# SAE_Shifter_Schem_no_micro.net
KiCad netlist of a schematic drawn in EAGLE
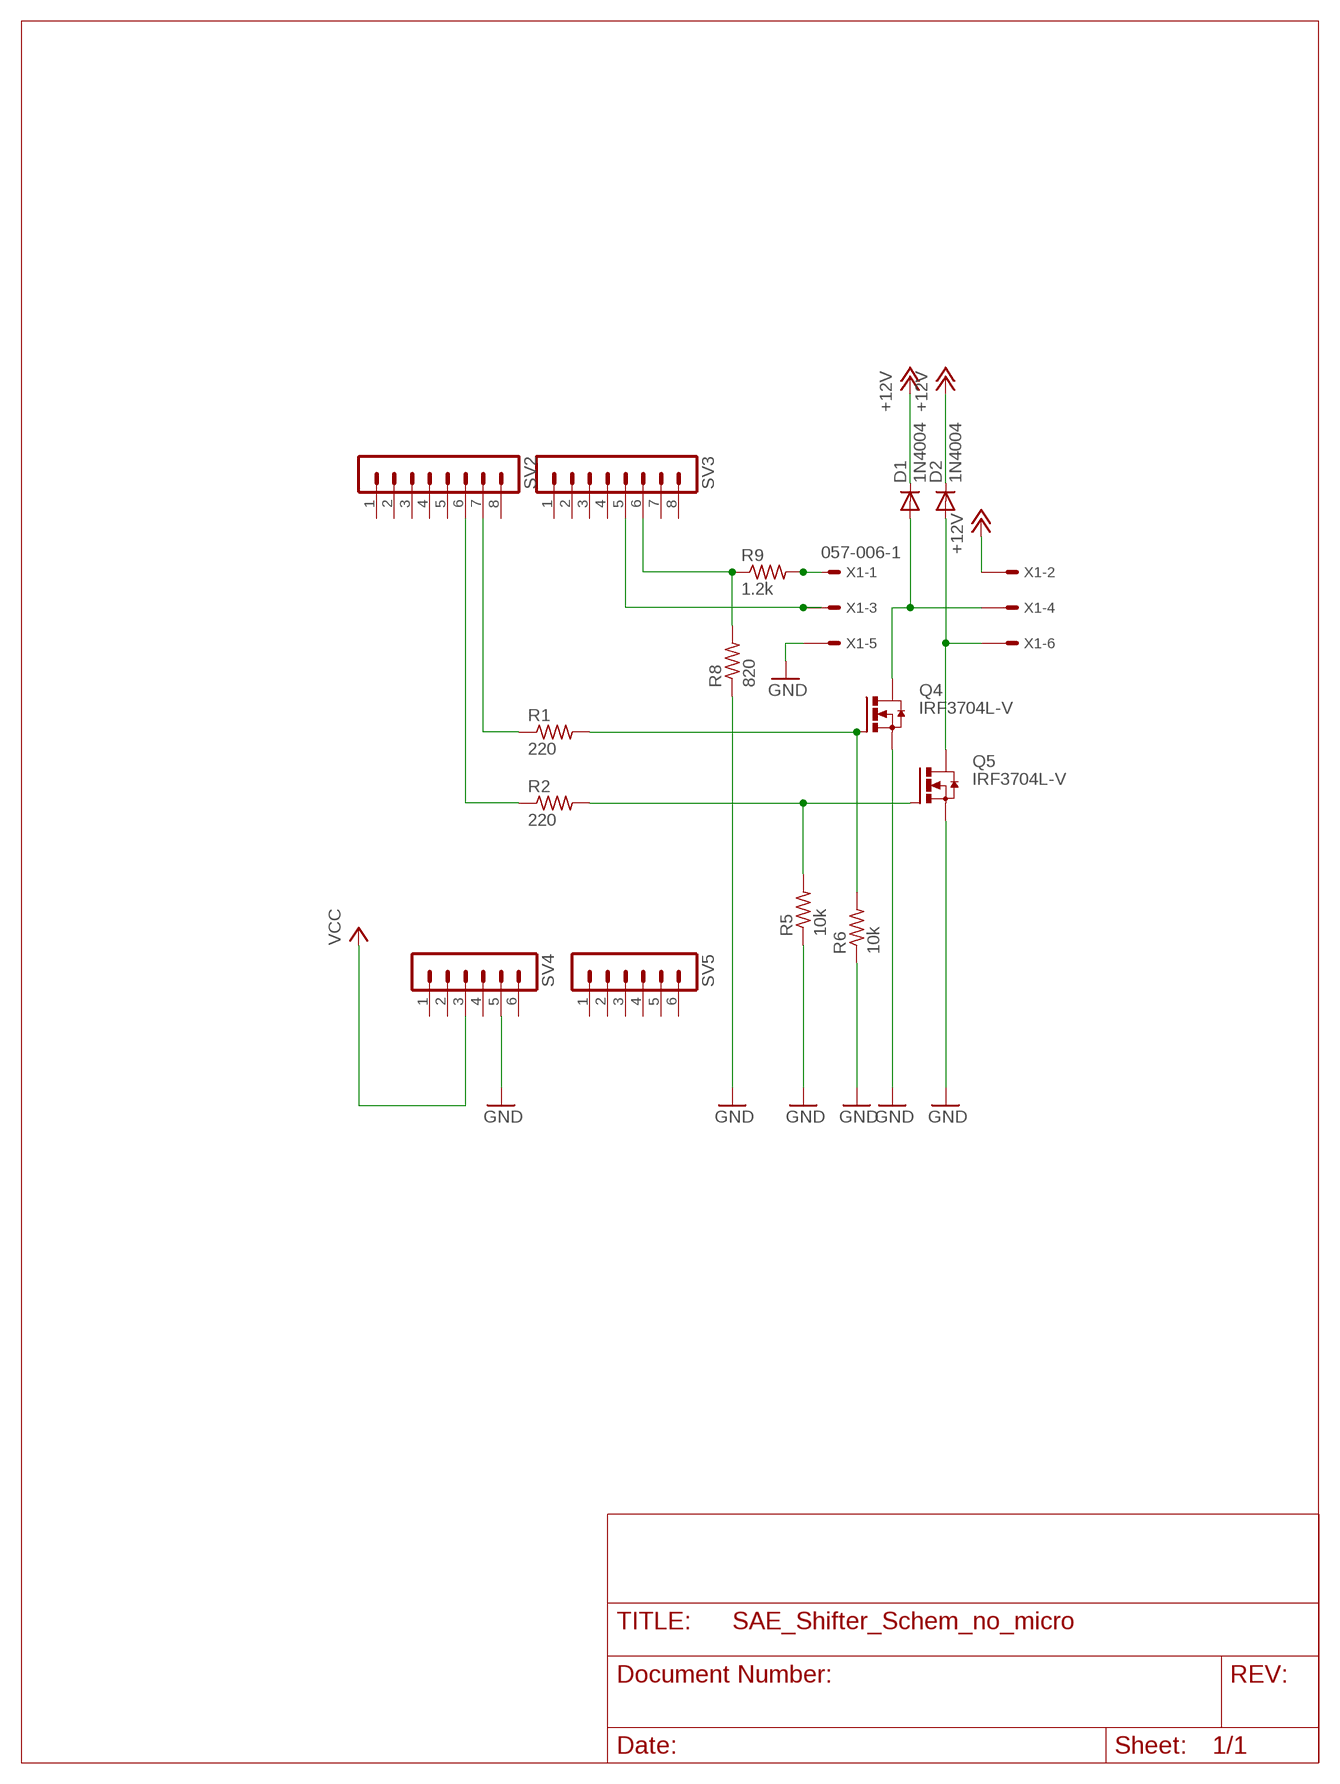
[diagram p0: schematic, sheet 1]

(export (version "E")
  (design (tool "Eeschema 10.0.6"))
  (components
    (comp (ref "D1")
      (value "1N4004")
      (footprint "eagle-import:DO41-10")
      (libsource (lib "eagle-import") (part "1N4004"))
    )
    (comp (ref "D2")
      (value "1N4004")
      (footprint "eagle-import:DO41-10")
      (libsource (lib "eagle-import") (part "1N4004"))
    )
    (comp (ref "Q4")
      (value "IRF3704L-V")
      (footprint "eagle-import:TO262-V")
      (libsource (lib "eagle-import") (part "IRF3704L-V"))
    )
    (comp (ref "Q5")
      (value "IRF3704L-V")
      (footprint "eagle-import:TO262-V")
      (libsource (lib "eagle-import") (part "IRF3704L-V"))
    )
    (comp (ref "R1")
      (value "220")
      (footprint "eagle-import:0207_10")
      (libsource (lib "eagle-import") (part "R-US_0207/10"))
    )
    (comp (ref "R2")
      (value "220")
      (footprint "eagle-import:0207_10")
      (libsource (lib "eagle-import") (part "R-US_0207/10"))
    )
    (comp (ref "R5")
      (value "10k")
      (footprint "eagle-import:0207_10")
      (libsource (lib "eagle-import") (part "R-US_0207/10"))
    )
    (comp (ref "R6")
      (value "10k")
      (footprint "eagle-import:0207_10")
      (libsource (lib "eagle-import") (part "R-US_0207/10"))
    )
    (comp (ref "R8")
      (value "820")
      (footprint "eagle-import:0207_10")
      (libsource (lib "eagle-import") (part "R-US_0207/10"))
    )
    (comp (ref "R9")
      (value "1.2k")
      (footprint "eagle-import:0207_10")
      (libsource (lib "eagle-import") (part "R-US_0207/10"))
    )
    (comp (ref "SV2")
      (value "MA08-1")
      (footprint "eagle-import:MA08-1")
      (libsource (lib "eagle-import") (part "MA08-1"))
    )
    (comp (ref "SV3")
      (value "MA08-1")
      (footprint "eagle-import:MA08-1")
      (libsource (lib "eagle-import") (part "MA08-1"))
    )
    (comp (ref "SV4")
      (value "MA06-1")
      (footprint "eagle-import:MA06-1")
      (libsource (lib "eagle-import") (part "MA06-1"))
    )
    (comp (ref "SV5")
      (value "MA06-1")
      (footprint "eagle-import:MA06-1")
      (libsource (lib "eagle-import") (part "MA06-1"))
    )
    (comp (ref "X1")
      (value "057-006-1")
      (footprint "eagle-import:057-006-1")
      (libsource (lib "eagle-import") (part "057-006-1"))
    )
  )
  (nets
    (net (code "1") (name "+12V") (class "Default")
      (node (ref "D1") (pin "C") (pinfunction "C_C") (pintype "passive"))
      (node (ref "D2") (pin "C") (pinfunction "C_C") (pintype "passive"))
      (node (ref "X1") (pin "2") (pinfunction "S_2") (pintype "passive"))
    )
    (net (code "2") (name "GND") (class "Default")
      (node (ref "Q4") (pin "3") (pinfunction "S_3") (pintype "passive"))
      (node (ref "Q5") (pin "3") (pinfunction "S_3") (pintype "passive"))
      (node (ref "R5") (pin "1") (pinfunction "1_1") (pintype "passive"))
      (node (ref "R6") (pin "1") (pinfunction "1_1") (pintype "passive"))
      (node (ref "R8") (pin "1") (pinfunction "1_1") (pintype "passive"))
      (node (ref "SV4") (pin "5") (pinfunction "5_5") (pintype "passive"))
      (node (ref "X1") (pin "5") (pinfunction "S_5") (pintype "passive"))
    )
    (net (code "3") (name "Net-(Q4-D)") (class "Default")
      (node (ref "D1") (pin "A") (pinfunction "A_A") (pintype "passive"))
      (node (ref "Q4") (pin "2") (pinfunction "D_2") (pintype "passive"))
      (node (ref "X1") (pin "4") (pinfunction "S_4") (pintype "passive"))
    )
    (net (code "4") (name "Net-(Q4-G)") (class "Default")
      (node (ref "Q4") (pin "1") (pinfunction "G_1") (pintype "passive"))
      (node (ref "R1") (pin "2") (pinfunction "2_2") (pintype "passive"))
      (node (ref "R6") (pin "2") (pinfunction "2_2") (pintype "passive"))
    )
    (net (code "5") (name "Net-(Q5-D)") (class "Default")
      (node (ref "D2") (pin "A") (pinfunction "A_A") (pintype "passive"))
      (node (ref "Q5") (pin "2") (pinfunction "D_2") (pintype "passive"))
      (node (ref "X1") (pin "6") (pinfunction "S_6") (pintype "passive"))
    )
    (net (code "6") (name "Net-(Q5-G)") (class "Default")
      (node (ref "Q5") (pin "1") (pinfunction "G_1") (pintype "passive"))
      (node (ref "R2") (pin "2") (pinfunction "2_2") (pintype "passive"))
      (node (ref "R5") (pin "2") (pinfunction "2_2") (pintype "passive"))
    )
    (net (code "7") (name "Net-(R1-Pad1)") (class "Default")
      (node (ref "R1") (pin "1") (pinfunction "1_1") (pintype "passive"))
      (node (ref "SV2") (pin "7") (pinfunction "7_7") (pintype "passive"))
    )
    (net (code "8") (name "Net-(R2-Pad1)") (class "Default")
      (node (ref "R2") (pin "1") (pinfunction "1_1") (pintype "passive"))
      (node (ref "SV2") (pin "6") (pinfunction "6_6") (pintype "passive"))
    )
    (net (code "9") (name "Net-(R8-Pad2)") (class "Default")
      (node (ref "R8") (pin "2") (pinfunction "2_2") (pintype "passive"))
      (node (ref "R9") (pin "1") (pinfunction "1_1") (pintype "passive"))
      (node (ref "SV3") (pin "6") (pinfunction "6_6") (pintype "passive"))
    )
    (net (code "10") (name "Net-(X1A-S)") (class "Default")
      (node (ref "R9") (pin "2") (pinfunction "2_2") (pintype "passive"))
      (node (ref "X1") (pin "1") (pinfunction "S_1") (pintype "passive"))
    )
    (net (code "11") (name "Net-(X1C-S)") (class "Default")
      (node (ref "SV3") (pin "5") (pinfunction "5_5") (pintype "passive"))
      (node (ref "X1") (pin "3") (pinfunction "S_3") (pintype "passive"))
    )
    (net (code "12") (name "VCC") (class "Default")
      (node (ref "SV4") (pin "3") (pinfunction "3_3") (pintype "passive"))
    )
    (net (code "13") (name "unconnected-(SV2-Pad1)") (class "Default")
      (node (ref "SV2") (pin "1") (pinfunction "1_1") (pintype "passive"))
    )
    (net (code "14") (name "unconnected-(SV2-Pad2)") (class "Default")
      (node (ref "SV2") (pin "2") (pinfunction "2_2") (pintype "passive"))
    )
    (net (code "15") (name "unconnected-(SV2-Pad3)") (class "Default")
      (node (ref "SV2") (pin "3") (pinfunction "3_3") (pintype "passive"))
    )
    (net (code "16") (name "unconnected-(SV2-Pad4)") (class "Default")
      (node (ref "SV2") (pin "4") (pinfunction "4_4") (pintype "passive"))
    )
    (net (code "17") (name "unconnected-(SV2-Pad5)") (class "Default")
      (node (ref "SV2") (pin "5") (pinfunction "5_5") (pintype "passive"))
    )
    (net (code "18") (name "unconnected-(SV2-Pad8)") (class "Default")
      (node (ref "SV2") (pin "8") (pinfunction "8_8") (pintype "passive"))
    )
    (net (code "19") (name "unconnected-(SV3-Pad1)") (class "Default")
      (node (ref "SV3") (pin "1") (pinfunction "1_1") (pintype "passive"))
    )
    (net (code "20") (name "unconnected-(SV3-Pad2)") (class "Default")
      (node (ref "SV3") (pin "2") (pinfunction "2_2") (pintype "passive"))
    )
    (net (code "21") (name "unconnected-(SV3-Pad3)") (class "Default")
      (node (ref "SV3") (pin "3") (pinfunction "3_3") (pintype "passive"))
    )
    (net (code "22") (name "unconnected-(SV3-Pad4)") (class "Default")
      (node (ref "SV3") (pin "4") (pinfunction "4_4") (pintype "passive"))
    )
    (net (code "23") (name "unconnected-(SV3-Pad7)") (class "Default")
      (node (ref "SV3") (pin "7") (pinfunction "7_7") (pintype "passive"))
    )
    (net (code "24") (name "unconnected-(SV3-Pad8)") (class "Default")
      (node (ref "SV3") (pin "8") (pinfunction "8_8") (pintype "passive"))
    )
    (net (code "25") (name "unconnected-(SV4-Pad1)") (class "Default")
      (node (ref "SV4") (pin "1") (pinfunction "1_1") (pintype "passive"))
    )
    (net (code "26") (name "unconnected-(SV4-Pad2)") (class "Default")
      (node (ref "SV4") (pin "2") (pinfunction "2_2") (pintype "passive"))
    )
    (net (code "27") (name "unconnected-(SV4-Pad4)") (class "Default")
      (node (ref "SV4") (pin "4") (pinfunction "4_4") (pintype "passive"))
    )
    (net (code "28") (name "unconnected-(SV4-Pad6)") (class "Default")
      (node (ref "SV4") (pin "6") (pinfunction "6_6") (pintype "passive"))
    )
    (net (code "29") (name "unconnected-(SV5-Pad1)") (class "Default")
      (node (ref "SV5") (pin "1") (pinfunction "1_1") (pintype "passive"))
    )
    (net (code "30") (name "unconnected-(SV5-Pad2)") (class "Default")
      (node (ref "SV5") (pin "2") (pinfunction "2_2") (pintype "passive"))
    )
    (net (code "31") (name "unconnected-(SV5-Pad3)") (class "Default")
      (node (ref "SV5") (pin "3") (pinfunction "3_3") (pintype "passive"))
    )
    (net (code "32") (name "unconnected-(SV5-Pad4)") (class "Default")
      (node (ref "SV5") (pin "4") (pinfunction "4_4") (pintype "passive"))
    )
    (net (code "33") (name "unconnected-(SV5-Pad5)") (class "Default")
      (node (ref "SV5") (pin "5") (pinfunction "5_5") (pintype "passive"))
    )
    (net (code "34") (name "unconnected-(SV5-Pad6)") (class "Default")
      (node (ref "SV5") (pin "6") (pinfunction "6_6") (pintype "passive"))
    )
  )
)
